# RoverPower.net
KiCad netlist of a schematic drawn in EAGLE
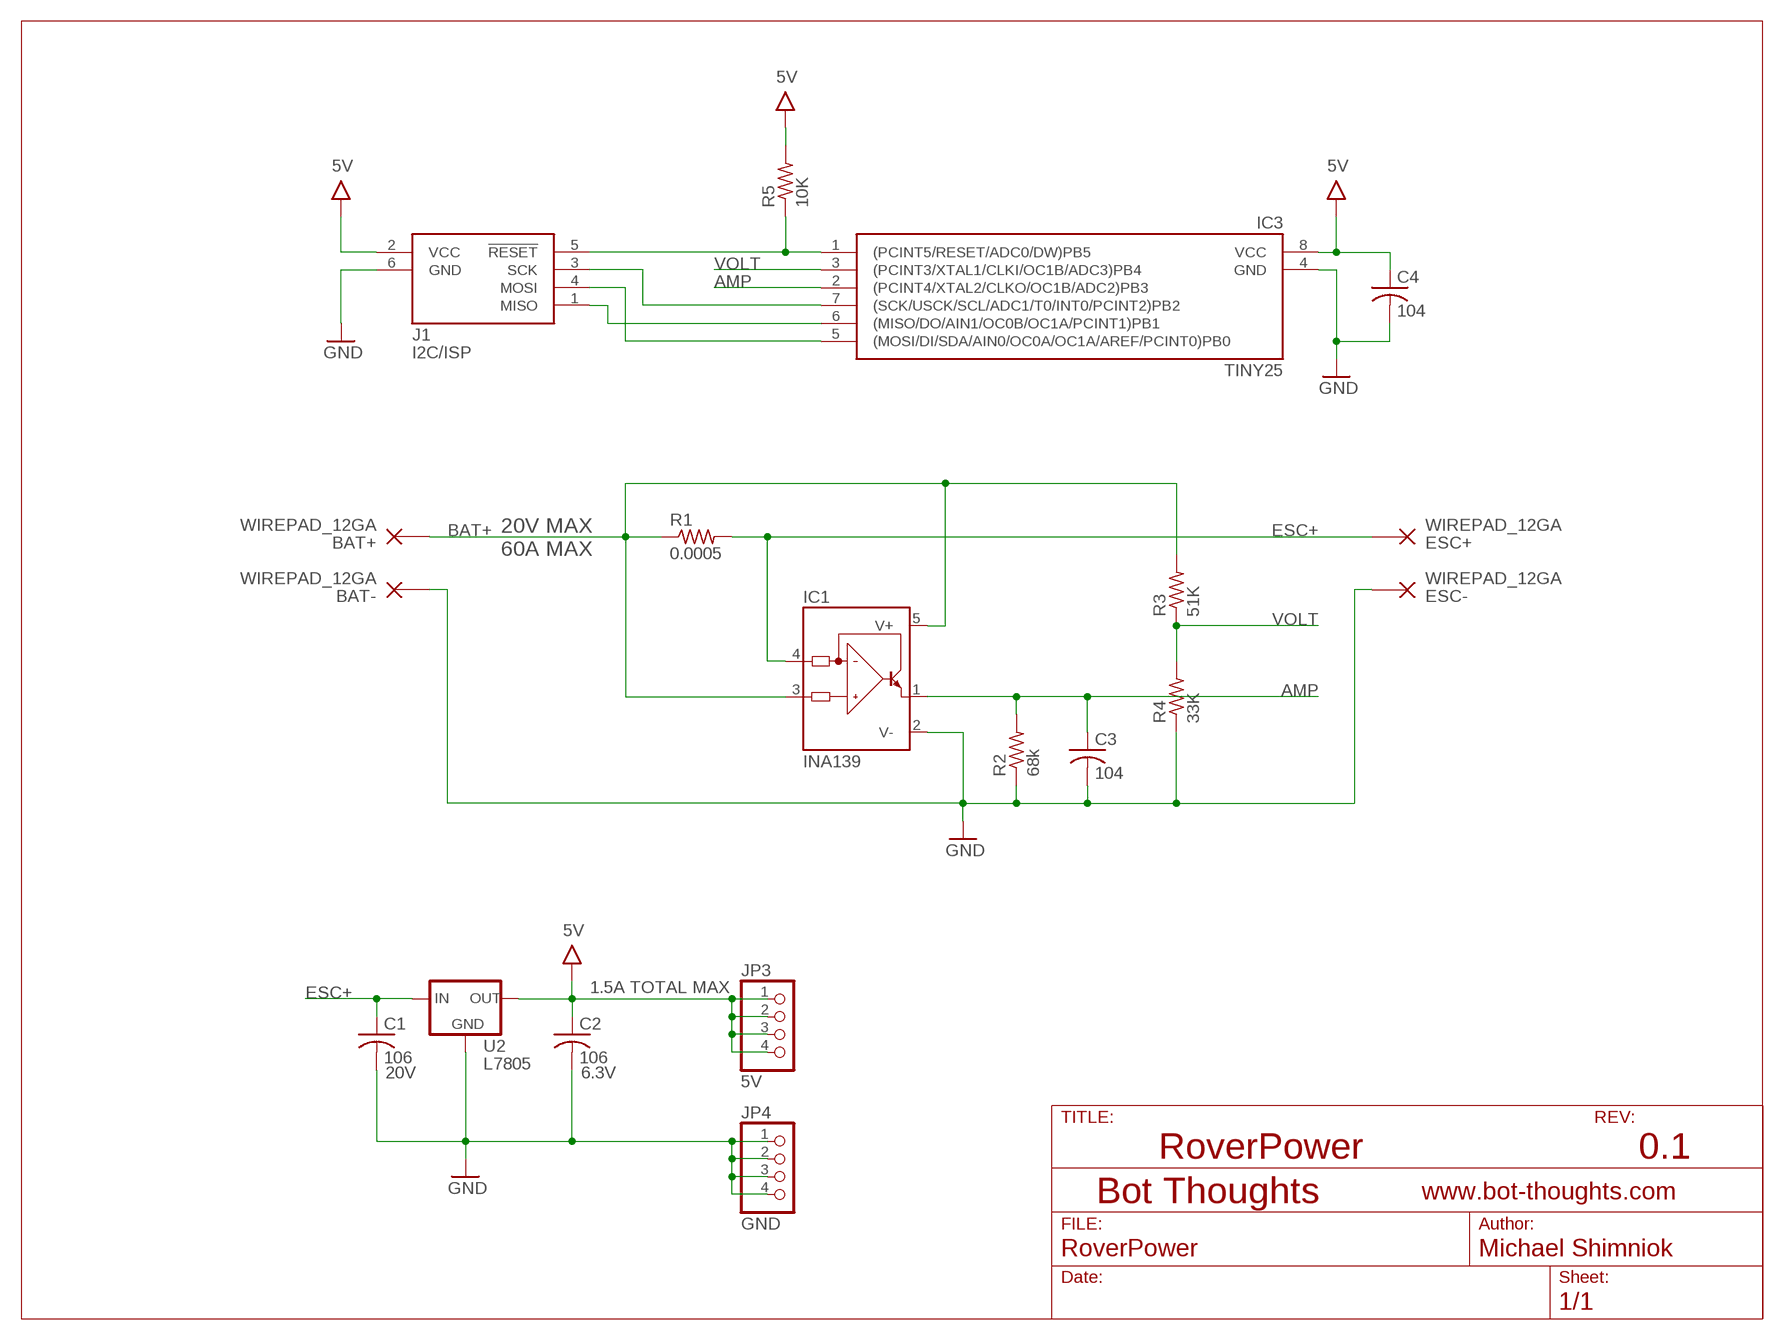
[diagram p0: schematic, sheet 1]

(export (version "E")
  (design (tool "Eeschema 10.0.6"))
  (components
    (comp (ref "BAT+")
      (value "WIREPAD_12GA")
      (footprint "eagle-import:PAD_12GA")
      (libsource (lib "eagle-import") (part "WIREPAD_12GA"))
    )
    (comp (ref "BAT-")
      (value "WIREPAD_12GA")
      (footprint "eagle-import:PAD_12GA")
      (libsource (lib "eagle-import") (part "WIREPAD_12GA"))
    )
    (comp (ref "C1")
      (value "106")
      (footprint "eagle-import:C1206")
      (fields (field (name "VOLTAGE") "20V"))
      (libsource (lib "eagle-import") (part "C-USC1206"))
    )
    (comp (ref "C2")
      (value "106")
      (footprint "eagle-import:C1206")
      (fields (field (name "VOLTAGE") "6.3V"))
      (libsource (lib "eagle-import") (part "C-USC1206"))
    )
    (comp (ref "C3")
      (value "104")
      (footprint "eagle-import:C0603")
      (libsource (lib "eagle-import") (part "resistor_C-USC0603"))
    )
    (comp (ref "C4")
      (value "104")
      (footprint "eagle-import:C0603")
      (libsource (lib "eagle-import") (part "C-USC0603"))
    )
    (comp (ref "ESC+")
      (value "WIREPAD_12GA")
      (footprint "eagle-import:PAD_12GA")
      (libsource (lib "eagle-import") (part "WIREPAD_12GA"))
    )
    (comp (ref "ESC-")
      (value "WIREPAD_12GA")
      (footprint "eagle-import:PAD_12GA")
      (libsource (lib "eagle-import") (part "WIREPAD_12GA"))
    )
    (comp (ref "IC1")
      (value "INA139")
      (footprint "eagle-import:SOT23-5")
      (fields (field (name "MF") "TEXAS INSTRUMENTS") (field (name "MPN") "INA168NA/250"))
      (libsource (lib "eagle-import") (part "INA168"))
    )
    (comp (ref "IC3")
      (value "TINY25")
      (footprint "eagle-import:SOIC8")
      (libsource (lib "eagle-import") (part "TINY25/45/85-20SU"))
    )
    (comp (ref "J1")
      (value "I2C/ISP")
      (footprint "eagle-import:CON6P2R")
      (libsource (lib "eagle-import") (part "AVRISP6"))
    )
    (comp (ref "JP3")
      (value "5V")
      (footprint "eagle-import:1X04-S")
      (libsource (lib "eagle-import") (part "PINHD-1X04_2.54-S"))
    )
    (comp (ref "JP4")
      (value "GND")
      (footprint "eagle-import:1X04-S")
      (libsource (lib "eagle-import") (part "PINHD-1X04_2.54-S"))
    )
    (comp (ref "R1")
      (value "0.0005")
      (footprint "eagle-import:R2512")
      (libsource (lib "eagle-import") (part "R-US__2512"))
    )
    (comp (ref "R2")
      (value "68k")
      (footprint "eagle-import:R0603")
      (libsource (lib "eagle-import") (part "R-US_R0603"))
    )
    (comp (ref "R3")
      (value "51K")
      (footprint "eagle-import:R0603")
      (libsource (lib "eagle-import") (part "resistor_R-US_R0603"))
    )
    (comp (ref "R4")
      (value "33K")
      (footprint "eagle-import:R0603")
      (libsource (lib "eagle-import") (part "resistor_R-US_R0603"))
    )
    (comp (ref "R5")
      (value "10K")
      (footprint "eagle-import:R0603")
      (libsource (lib "eagle-import") (part "resistor_R-US_R0603"))
    )
    (comp (ref "U2")
      (value "L7805")
      (footprint "eagle-import:D2PAK")
      (libsource (lib "eagle-import") (part "L78XXD2TT"))
    )
  )
  (nets
    (net (code "1") (name "/AMP") (class "Default")
      (node (ref "C3") (pin "1") (pinfunction "1_1") (pintype "passive"))
      (node (ref "IC1") (pin "1") (pinfunction "OUT_1") (pintype "output"))
      (node (ref "IC3") (pin "2") (pinfunction "(PCINT4/XTAL2/CLKO/OC1B/ADC2)PB3_2") (pintype "bidirectional"))
      (node (ref "R2") (pin "2") (pinfunction "2_2") (pintype "passive"))
    )
    (net (code "2") (name "/BAT+") (class "Default")
      (node (ref "BAT+") (pin "P$1") (pinfunction "P_P$1") (pintype "bidirectional"))
      (node (ref "IC1") (pin "3") (pinfunction "IN+_3") (pintype "input"))
      (node (ref "IC1") (pin "5") (pinfunction "V+_5") (pintype "power_in"))
      (node (ref "R1") (pin "P$1") (pinfunction "1_P$1") (pintype "passive"))
      (node (ref "R3") (pin "2") (pinfunction "2_2") (pintype "passive"))
    )
    (net (code "3") (name "/ESC+") (class "Default")
      (node (ref "C1") (pin "1") (pinfunction "1_1") (pintype "passive"))
      (node (ref "ESC+") (pin "P$1") (pinfunction "P_P$1") (pintype "bidirectional"))
      (node (ref "IC1") (pin "4") (pinfunction "IN-_4") (pintype "input"))
      (node (ref "R1") (pin "P$2") (pinfunction "2_P$2") (pintype "passive"))
      (node (ref "U2") (pin "1") (pinfunction "IN_1") (pintype "input"))
    )
    (net (code "4") (name "/VOLT") (class "Default")
      (node (ref "IC3") (pin "3") (pinfunction "(PCINT3/XTAL1/CLKI/OC1B/ADC3)PB4_3") (pintype "bidirectional"))
      (node (ref "R3") (pin "1") (pinfunction "1_1") (pintype "passive"))
      (node (ref "R4") (pin "2") (pinfunction "2_2") (pintype "passive"))
    )
    (net (code "5") (name "5V") (class "Default")
      (node (ref "C2") (pin "1") (pinfunction "1_1") (pintype "passive"))
      (node (ref "C4") (pin "1") (pinfunction "1_1") (pintype "passive"))
      (node (ref "IC3") (pin "8") (pinfunction "VCC_8") (pintype "power_in"))
      (node (ref "J1") (pin "2") (pinfunction "VCC_2") (pintype "power_in"))
      (node (ref "JP3") (pin "1") (pinfunction "1_1") (pintype "passive"))
      (node (ref "JP3") (pin "2") (pinfunction "2_2") (pintype "passive"))
      (node (ref "JP3") (pin "3") (pinfunction "3_3") (pintype "passive"))
      (node (ref "JP3") (pin "4") (pinfunction "4_4") (pintype "passive"))
      (node (ref "R5") (pin "2") (pinfunction "2_2") (pintype "passive"))
      (node (ref "U2") (pin "3") (pinfunction "OUT_3") (pintype "passive"))
    )
    (net (code "6") (name "GND") (class "Default")
      (node (ref "BAT-") (pin "P$1") (pinfunction "P_P$1") (pintype "bidirectional"))
      (node (ref "C1") (pin "2") (pinfunction "2_2") (pintype "passive"))
      (node (ref "C2") (pin "2") (pinfunction "2_2") (pintype "passive"))
      (node (ref "C3") (pin "2") (pinfunction "2_2") (pintype "passive"))
      (node (ref "C4") (pin "2") (pinfunction "2_2") (pintype "passive"))
      (node (ref "ESC-") (pin "P$1") (pinfunction "P_P$1") (pintype "bidirectional"))
      (node (ref "IC1") (pin "2") (pinfunction "V-_2") (pintype "power_in"))
      (node (ref "IC3") (pin "4") (pinfunction "GND_4") (pintype "power_in"))
      (node (ref "J1") (pin "6") (pinfunction "GND_6") (pintype "power_in"))
      (node (ref "JP4") (pin "1") (pinfunction "1_1") (pintype "passive"))
      (node (ref "JP4") (pin "2") (pinfunction "2_2") (pintype "passive"))
      (node (ref "JP4") (pin "3") (pinfunction "3_3") (pintype "passive"))
      (node (ref "JP4") (pin "4") (pinfunction "4_4") (pintype "passive"))
      (node (ref "R2") (pin "1") (pinfunction "1_1") (pintype "passive"))
      (node (ref "R4") (pin "1") (pinfunction "1_1") (pintype "passive"))
      (node (ref "U2") (pin "2") (pinfunction "GND_2") (pintype "input"))
    )
    (net (code "7") (name "Net-(IC3-(MISO{slash}DO{slash}AIN1{slash}OC0B{slash}OC1A{slash}PCINT1)PB1)") (class "Default")
      (node (ref "IC3") (pin "6") (pinfunction "(MISO/DO/AIN1/OC0B/OC1A/PCINT1)PB1_6") (pintype "bidirectional"))
      (node (ref "J1") (pin "1") (pinfunction "MISO_1") (pintype "input"))
    )
    (net (code "8") (name "Net-(IC3-(MOSI{slash}DI{slash}SDA{slash}AIN0{slash}OC0A{slash}OC1A{slash}AREF{slash}PCINT0)PB0)") (class "Default")
      (node (ref "IC3") (pin "5") (pinfunction "(MOSI/DI/SDA/AIN0/OC0A/OC1A/AREF/PCINT0)PB0_5") (pintype "bidirectional"))
      (node (ref "J1") (pin "4") (pinfunction "MOSI_4") (pintype "output"))
    )
    (net (code "9") (name "Net-(IC3-(PCINT5{slash}RESET{slash}ADC0{slash}DW)PB5)") (class "Default")
      (node (ref "IC3") (pin "1") (pinfunction "(PCINT5/RESET/ADC0/DW)PB5_1") (pintype "bidirectional"))
      (node (ref "J1") (pin "5") (pinfunction "~{RESET}_5") (pintype "output"))
      (node (ref "R5") (pin "1") (pinfunction "1_1") (pintype "passive"))
    )
    (net (code "10") (name "Net-(IC3-(SCK{slash}USCK{slash}SCL{slash}ADC1{slash}T0{slash}INT0{slash}PCINT2)PB2)") (class "Default")
      (node (ref "IC3") (pin "7") (pinfunction "(SCK/USCK/SCL/ADC1/T0/INT0/PCINT2)PB2_7") (pintype "bidirectional"))
      (node (ref "J1") (pin "3") (pinfunction "SCK_3") (pintype "output"))
    )
  )
)
